# PROC054D_AWR_2_AWR_3_LC_Filtering.net
KiCad netlist of a schematic drawn in Altium Designer
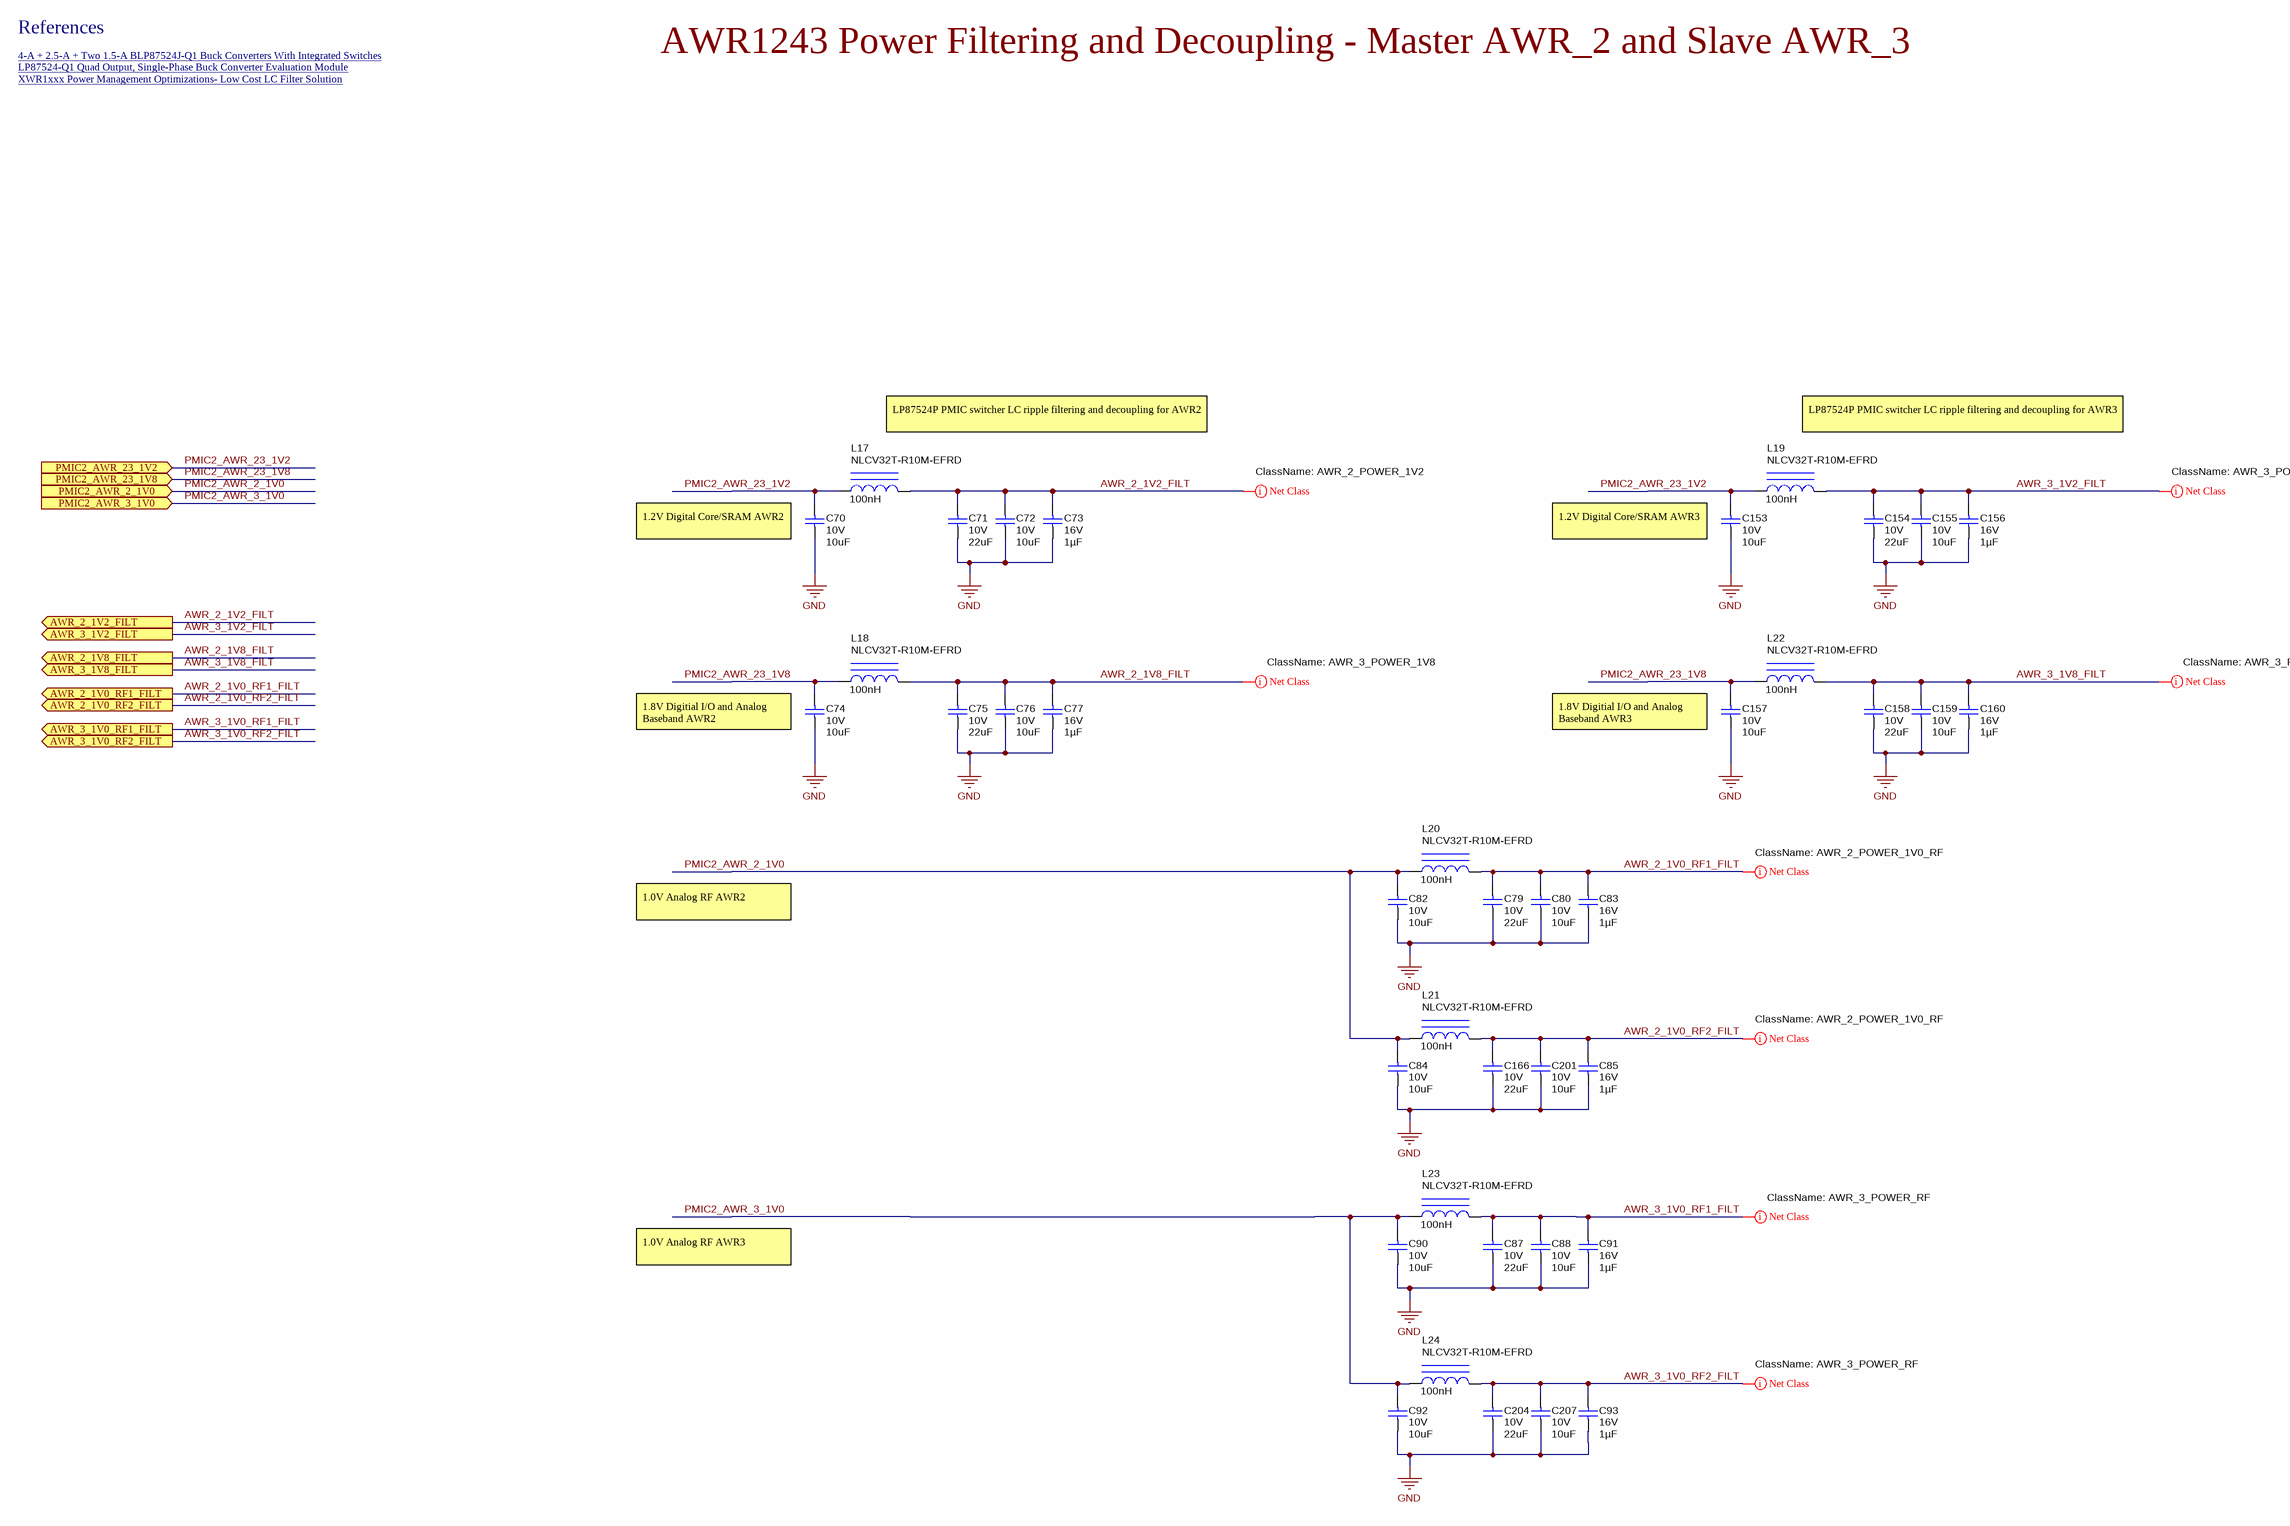
[diagram p0: PROC054D_AWR_2_AWR_3_LC_Filtering.SchDoc]

(export (version "E")
  (design (tool "Eeschema 10.0.6"))
  (components
    (comp (ref "C70")
      (value "GCM21BR71A106KE22L")
      (footprint "0805L")
      (description "CAP, CERM, 10 uF, 10 V, +/- 10%, X7R, 0805")
      (fields
        (field (name "MANUFACTURER") "MuRata")
        (field (name "VDC_V") "10V")
        (field (name "VALUEDISPLAYED") "10uF")
        (field (name "PUBLISHER") "Texas Instruments")
      )
      (libsource (lib "Altium Vault - TI") (part "Capacitor"))
    )
    (comp (ref "C71")
      (value "GCM31CR71A226KE02")
      (footprint "1206_180L")
      (description "CAP, CERM, 22 uF, 10 V, +/- 10%, X7R, AEC-Q200 Grade 1, 1206")
      (fields
        (field (name "MANUFACTURER") "MuRata")
        (field (name "VDC_V") "10V")
        (field (name "VALUEDISPLAYED") "22uF")
        (field (name "PUBLISHER") "Texas Instruments")
      )
      (libsource (lib "Altium Vault - TI") (part "Capacitor"))
    )
    (comp (ref "C72")
      (value "GCM21BR71A106KE22L")
      (footprint "0805L")
      (description "CAP, CERM, 10 uF, 10 V, +/- 10%, X7R, 0805")
      (fields
        (field (name "MANUFACTURER") "MuRata")
        (field (name "VDC_V") "10V")
        (field (name "VALUEDISPLAYED") "10uF")
        (field (name "PUBLISHER") "Texas Instruments")
      )
      (libsource (lib "Altium Vault - TI") (part "Capacitor"))
    )
    (comp (ref "C73")
      (value "GCM188R71C105KA64J")
      (footprint "0603S")
      (description "CAP, CERM, 1 µF, 16 V,+/- 10%, X7R, AEC-Q200 Grade 1, 0603")
      (fields
        (field (name "MANUFACTURER") "MuRata")
        (field (name "VDC_V") "16V")
        (field (name "VALUEDISPLAYED") "1µF")
      )
      (libsource (lib "Altium Vault - TI") (part "Capacitor"))
    )
    (comp (ref "C74")
      (value "GCM21BR71A106KE22L")
      (footprint "0805L")
      (description "CAP, CERM, 10 uF, 10 V, +/- 10%, X7R, 0805")
      (fields
        (field (name "MANUFACTURER") "MuRata")
        (field (name "VDC_V") "10V")
        (field (name "VALUEDISPLAYED") "10uF")
        (field (name "PUBLISHER") "Texas Instruments")
      )
      (libsource (lib "Altium Vault - TI") (part "Capacitor"))
    )
    (comp (ref "C75")
      (value "GCM31CR71A226KE02")
      (footprint "1206_180L")
      (description "CAP, CERM, 22 uF, 10 V, +/- 10%, X7R, AEC-Q200 Grade 1, 1206")
      (fields
        (field (name "MANUFACTURER") "MuRata")
        (field (name "VDC_V") "10V")
        (field (name "VALUEDISPLAYED") "22uF")
        (field (name "PUBLISHER") "Texas Instruments")
      )
      (libsource (lib "Altium Vault - TI") (part "Capacitor"))
    )
    (comp (ref "C76")
      (value "GCM21BR71A106KE22L")
      (footprint "0805L")
      (description "CAP, CERM, 10 uF, 10 V, +/- 10%, X7R, 0805")
      (fields
        (field (name "MANUFACTURER") "MuRata")
        (field (name "VDC_V") "10V")
        (field (name "VALUEDISPLAYED") "10uF")
        (field (name "PUBLISHER") "Texas Instruments")
      )
      (libsource (lib "Altium Vault - TI") (part "Capacitor"))
    )
    (comp (ref "C77")
      (value "GCM188R71C105KA64J")
      (footprint "0603S")
      (description "CAP, CERM, 1 µF, 16 V,+/- 10%, X7R, AEC-Q200 Grade 1, 0603")
      (fields
        (field (name "MANUFACTURER") "MuRata")
        (field (name "VDC_V") "16V")
        (field (name "VALUEDISPLAYED") "1µF")
      )
      (libsource (lib "Altium Vault - TI") (part "Capacitor"))
    )
    (comp (ref "C79")
      (value "GCM31CR71A226KE02")
      (footprint "1206_180L")
      (description "CAP, CERM, 22 uF, 10 V, +/- 10%, X7R, AEC-Q200 Grade 1, 1206")
      (fields
        (field (name "MANUFACTURER") "MuRata")
        (field (name "VDC_V") "10V")
        (field (name "VALUEDISPLAYED") "22uF")
        (field (name "PUBLISHER") "Texas Instruments")
      )
      (libsource (lib "Altium Vault - TI") (part "Capacitor"))
    )
    (comp (ref "C80")
      (value "GCM21BR71A106KE22L")
      (footprint "0805L")
      (description "CAP, CERM, 10 uF, 10 V, +/- 10%, X7R, 0805")
      (fields
        (field (name "MANUFACTURER") "MuRata")
        (field (name "VDC_V") "10V")
        (field (name "VALUEDISPLAYED") "10uF")
        (field (name "PUBLISHER") "Texas Instruments")
      )
      (libsource (lib "Altium Vault - TI") (part "Capacitor"))
    )
    (comp (ref "C82")
      (value "GCM21BR71A106KE22L")
      (footprint "0805L")
      (description "CAP, CERM, 10 uF, 10 V, +/- 10%, X7R, 0805")
      (fields
        (field (name "MANUFACTURER") "MuRata")
        (field (name "VDC_V") "10V")
        (field (name "VALUEDISPLAYED") "10uF")
        (field (name "PUBLISHER") "Texas Instruments")
      )
      (libsource (lib "Altium Vault - TI") (part "Capacitor"))
    )
    (comp (ref "C83")
      (value "GCM188R71C105KA64J")
      (footprint "0603S")
      (description "CAP, CERM, 1 µF, 16 V,+/- 10%, X7R, AEC-Q200 Grade 1, 0603")
      (fields
        (field (name "MANUFACTURER") "MuRata")
        (field (name "VDC_V") "16V")
        (field (name "VALUEDISPLAYED") "1µF")
      )
      (libsource (lib "Altium Vault - TI") (part "Capacitor"))
    )
    (comp (ref "C84")
      (value "GCM21BR71A106KE22L")
      (footprint "0805L")
      (description "CAP, CERM, 10 uF, 10 V, +/- 10%, X7R, 0805")
      (fields
        (field (name "MANUFACTURER") "MuRata")
        (field (name "VDC_V") "10V")
        (field (name "VALUEDISPLAYED") "10uF")
        (field (name "PUBLISHER") "Texas Instruments")
      )
      (libsource (lib "Altium Vault - TI") (part "Capacitor"))
    )
    (comp (ref "C85")
      (value "GCM188R71C105KA64J")
      (footprint "0603S")
      (description "CAP, CERM, 1 µF, 16 V,+/- 10%, X7R, AEC-Q200 Grade 1, 0603")
      (fields
        (field (name "MANUFACTURER") "MuRata")
        (field (name "VDC_V") "16V")
        (field (name "VALUEDISPLAYED") "1µF")
      )
      (libsource (lib "Altium Vault - TI") (part "Capacitor"))
    )
    (comp (ref "C87")
      (value "GCM31CR71A226KE02")
      (footprint "1206_180L")
      (description "CAP, CERM, 22 uF, 10 V, +/- 10%, X7R, AEC-Q200 Grade 1, 1206")
      (fields
        (field (name "MANUFACTURER") "MuRata")
        (field (name "VDC_V") "10V")
        (field (name "VALUEDISPLAYED") "22uF")
        (field (name "PUBLISHER") "Texas Instruments")
      )
      (libsource (lib "Altium Vault - TI") (part "Capacitor"))
    )
    (comp (ref "C88")
      (value "GCM21BR71A106KE22L")
      (footprint "0805L")
      (description "CAP, CERM, 10 uF, 10 V, +/- 10%, X7R, 0805")
      (fields
        (field (name "MANUFACTURER") "MuRata")
        (field (name "VDC_V") "10V")
        (field (name "VALUEDISPLAYED") "10uF")
        (field (name "PUBLISHER") "Texas Instruments")
      )
      (libsource (lib "Altium Vault - TI") (part "Capacitor"))
    )
    (comp (ref "C90")
      (value "GCM21BR71A106KE22L")
      (footprint "0805L")
      (description "CAP, CERM, 10 uF, 10 V, +/- 10%, X7R, 0805")
      (fields
        (field (name "MANUFACTURER") "MuRata")
        (field (name "VDC_V") "10V")
        (field (name "VALUEDISPLAYED") "10uF")
        (field (name "PUBLISHER") "Texas Instruments")
      )
      (libsource (lib "Altium Vault - TI") (part "Capacitor"))
    )
    (comp (ref "C91")
      (value "GCM188R71C105KA64J")
      (footprint "0603S")
      (description "CAP, CERM, 1 µF, 16 V,+/- 10%, X7R, AEC-Q200 Grade 1, 0603")
      (fields
        (field (name "MANUFACTURER") "MuRata")
        (field (name "VDC_V") "16V")
        (field (name "VALUEDISPLAYED") "1µF")
      )
      (libsource (lib "Altium Vault - TI") (part "Capacitor"))
    )
    (comp (ref "C92")
      (value "GCM21BR71A106KE22L")
      (footprint "0805L")
      (description "CAP, CERM, 10 uF, 10 V, +/- 10%, X7R, 0805")
      (fields
        (field (name "MANUFACTURER") "MuRata")
        (field (name "VDC_V") "10V")
        (field (name "VALUEDISPLAYED") "10uF")
        (field (name "PUBLISHER") "Texas Instruments")
      )
      (libsource (lib "Altium Vault - TI") (part "Capacitor"))
    )
    (comp (ref "C93")
      (value "GCM188R71C105KA64J")
      (footprint "0603S")
      (description "CAP, CERM, 1 µF, 16 V,+/- 10%, X7R, AEC-Q200 Grade 1, 0603")
      (fields
        (field (name "MANUFACTURER") "MuRata")
        (field (name "VDC_V") "16V")
        (field (name "VALUEDISPLAYED") "1µF")
      )
      (libsource (lib "Altium Vault - TI") (part "Capacitor"))
    )
    (comp (ref "C153")
      (value "GCM21BR71A106KE22L")
      (footprint "0805L")
      (description "CAP, CERM, 10 uF, 10 V, +/- 10%, X7R, 0805")
      (fields
        (field (name "MANUFACTURER") "MuRata")
        (field (name "VDC_V") "10V")
        (field (name "VALUEDISPLAYED") "10uF")
        (field (name "PUBLISHER") "Texas Instruments")
      )
      (libsource (lib "Altium Vault - TI") (part "Capacitor"))
    )
    (comp (ref "C154")
      (value "GCM31CR71A226KE02")
      (footprint "1206_180L")
      (description "CAP, CERM, 22 uF, 10 V, +/- 10%, X7R, AEC-Q200 Grade 1, 1206")
      (fields
        (field (name "MANUFACTURER") "MuRata")
        (field (name "VDC_V") "10V")
        (field (name "VALUEDISPLAYED") "22uF")
        (field (name "PUBLISHER") "Texas Instruments")
      )
      (libsource (lib "Altium Vault - TI") (part "Capacitor"))
    )
    (comp (ref "C155")
      (value "GCM21BR71A106KE22L")
      (footprint "0805L")
      (description "CAP, CERM, 10 uF, 10 V, +/- 10%, X7R, 0805")
      (fields
        (field (name "MANUFACTURER") "MuRata")
        (field (name "VDC_V") "10V")
        (field (name "VALUEDISPLAYED") "10uF")
        (field (name "PUBLISHER") "Texas Instruments")
      )
      (libsource (lib "Altium Vault - TI") (part "Capacitor"))
    )
    (comp (ref "C156")
      (value "GCM188R71C105KA64J")
      (footprint "0603S")
      (description "CAP, CERM, 1 µF, 16 V,+/- 10%, X7R, AEC-Q200 Grade 1, 0603")
      (fields
        (field (name "MANUFACTURER") "MuRata")
        (field (name "VDC_V") "16V")
        (field (name "VALUEDISPLAYED") "1µF")
      )
      (libsource (lib "Altium Vault - TI") (part "Capacitor"))
    )
    (comp (ref "C157")
      (value "GCM21BR71A106KE22L")
      (footprint "0805L")
      (description "CAP, CERM, 10 uF, 10 V, +/- 10%, X7R, 0805")
      (fields
        (field (name "MANUFACTURER") "MuRata")
        (field (name "VDC_V") "10V")
        (field (name "VALUEDISPLAYED") "10uF")
        (field (name "PUBLISHER") "Texas Instruments")
      )
      (libsource (lib "Altium Vault - TI") (part "Capacitor"))
    )
    (comp (ref "C158")
      (value "GCM31CR71A226KE02")
      (footprint "1206_180L")
      (description "CAP, CERM, 22 uF, 10 V, +/- 10%, X7R, AEC-Q200 Grade 1, 1206")
      (fields
        (field (name "MANUFACTURER") "MuRata")
        (field (name "VDC_V") "10V")
        (field (name "VALUEDISPLAYED") "22uF")
        (field (name "PUBLISHER") "Texas Instruments")
      )
      (libsource (lib "Altium Vault - TI") (part "Capacitor"))
    )
    (comp (ref "C159")
      (value "GCM21BR71A106KE22L")
      (footprint "0805L")
      (description "CAP, CERM, 10 uF, 10 V, +/- 10%, X7R, 0805")
      (fields
        (field (name "MANUFACTURER") "MuRata")
        (field (name "VDC_V") "10V")
        (field (name "VALUEDISPLAYED") "10uF")
        (field (name "PUBLISHER") "Texas Instruments")
      )
      (libsource (lib "Altium Vault - TI") (part "Capacitor"))
    )
    (comp (ref "C160")
      (value "GCM188R71C105KA64J")
      (footprint "0603S")
      (description "CAP, CERM, 1 µF, 16 V,+/- 10%, X7R, AEC-Q200 Grade 1, 0603")
      (fields
        (field (name "MANUFACTURER") "MuRata")
        (field (name "VDC_V") "16V")
        (field (name "VALUEDISPLAYED") "1µF")
      )
      (libsource (lib "Altium Vault - TI") (part "Capacitor"))
    )
    (comp (ref "C166")
      (value "GCM31CR71A226KE02")
      (footprint "1206_180L")
      (description "CAP, CERM, 22 uF, 10 V, +/- 10%, X7R, AEC-Q200 Grade 1, 1206")
      (fields
        (field (name "MANUFACTURER") "MuRata")
        (field (name "VDC_V") "10V")
        (field (name "VALUEDISPLAYED") "22uF")
        (field (name "PUBLISHER") "Texas Instruments")
      )
      (libsource (lib "Altium Vault - TI") (part "Capacitor"))
    )
    (comp (ref "C201")
      (value "GCM21BR71A106KE22L")
      (footprint "0805L")
      (description "CAP, CERM, 10 uF, 10 V, +/- 10%, X7R, 0805")
      (fields
        (field (name "MANUFACTURER") "MuRata")
        (field (name "VDC_V") "10V")
        (field (name "VALUEDISPLAYED") "10uF")
        (field (name "PUBLISHER") "Texas Instruments")
      )
      (libsource (lib "Altium Vault - TI") (part "Capacitor"))
    )
    (comp (ref "C204")
      (value "GCM31CR71A226KE02")
      (footprint "1206_180L")
      (description "CAP, CERM, 22 uF, 10 V, +/- 10%, X7R, AEC-Q200 Grade 1, 1206")
      (fields
        (field (name "MANUFACTURER") "MuRata")
        (field (name "VDC_V") "10V")
        (field (name "VALUEDISPLAYED") "22uF")
        (field (name "PUBLISHER") "Texas Instruments")
      )
      (libsource (lib "Altium Vault - TI") (part "Capacitor"))
    )
    (comp (ref "C207")
      (value "GCM21BR71A106KE22L")
      (footprint "0805L")
      (description "CAP, CERM, 10 uF, 10 V, +/- 10%, X7R, 0805")
      (fields
        (field (name "MANUFACTURER") "MuRata")
        (field (name "VDC_V") "10V")
        (field (name "VALUEDISPLAYED") "10uF")
        (field (name "PUBLISHER") "Texas Instruments")
      )
      (libsource (lib "Altium Vault - TI") (part "Capacitor"))
    )
    (comp (ref "L17")
      (value "NLCV32T-R10M-EFRD")
      (footprint "NLCV32")
      (description "Inductor, Wirewound, Ferrite, 100 nH, 2.85 A, 0.024 ohm, AEC-Q200 Grade 1, SMD")
      (fields
        (field (name "MANUFACTURER") "TDK")
        (field (name "PARTNUMBER") "NLCV32T-R10M-EFRD")
        (field (name "VALUEDISPLAYED") "100nH")
      )
      (libsource (lib "Altium Vault - TI") (part "CMP-0083745-1"))
    )
    (comp (ref "L18")
      (value "NLCV32T-R10M-EFRD")
      (footprint "NLCV32")
      (description "Inductor, Wirewound, Ferrite, 100 nH, 2.85 A, 0.024 ohm, AEC-Q200 Grade 1, SMD")
      (fields
        (field (name "MANUFACTURER") "TDK")
        (field (name "PARTNUMBER") "NLCV32T-R10M-EFRD")
        (field (name "VALUEDISPLAYED") "100nH")
      )
      (libsource (lib "Altium Vault - TI") (part "CMP-0083745-1"))
    )
    (comp (ref "L19")
      (value "NLCV32T-R10M-EFRD")
      (footprint "NLCV32")
      (description "Inductor, Wirewound, Ferrite, 100 nH, 2.85 A, 0.024 ohm, AEC-Q200 Grade 1, SMD")
      (fields
        (field (name "MANUFACTURER") "TDK")
        (field (name "PARTNUMBER") "NLCV32T-R10M-EFRD")
        (field (name "VALUEDISPLAYED") "100nH")
      )
      (libsource (lib "Altium Vault - TI") (part "CMP-0083745-1"))
    )
    (comp (ref "L20")
      (value "NLCV32T-R10M-EFRD")
      (footprint "NLCV32")
      (description "Inductor, Wirewound, Ferrite, 100 nH, 2.85 A, 0.024 ohm, AEC-Q200 Grade 1, SMD")
      (fields
        (field (name "MANUFACTURER") "TDK")
        (field (name "PARTNUMBER") "NLCV32T-R10M-EFRD")
        (field (name "VALUEDISPLAYED") "100nH")
      )
      (libsource (lib "Altium Vault - TI") (part "CMP-0083745-1"))
    )
    (comp (ref "L21")
      (value "NLCV32T-R10M-EFRD")
      (footprint "NLCV32")
      (description "Inductor, Wirewound, Ferrite, 100 nH, 2.85 A, 0.024 ohm, AEC-Q200 Grade 1, SMD")
      (fields
        (field (name "MANUFACTURER") "TDK")
        (field (name "PARTNUMBER") "NLCV32T-R10M-EFRD")
        (field (name "VALUEDISPLAYED") "100nH")
      )
      (libsource (lib "Altium Vault - TI") (part "CMP-0083745-1"))
    )
    (comp (ref "L22")
      (value "NLCV32T-R10M-EFRD")
      (footprint "NLCV32")
      (description "Inductor, Wirewound, Ferrite, 100 nH, 2.85 A, 0.024 ohm, AEC-Q200 Grade 1, SMD")
      (fields
        (field (name "MANUFACTURER") "TDK")
        (field (name "PARTNUMBER") "NLCV32T-R10M-EFRD")
        (field (name "VALUEDISPLAYED") "100nH")
      )
      (libsource (lib "Altium Vault - TI") (part "CMP-0083745-1"))
    )
    (comp (ref "L23")
      (value "NLCV32T-R10M-EFRD")
      (footprint "NLCV32")
      (description "Inductor, Wirewound, Ferrite, 100 nH, 2.85 A, 0.024 ohm, AEC-Q200 Grade 1, SMD")
      (fields
        (field (name "MANUFACTURER") "TDK")
        (field (name "PARTNUMBER") "NLCV32T-R10M-EFRD")
        (field (name "VALUEDISPLAYED") "100nH")
      )
      (libsource (lib "Altium Vault - TI") (part "CMP-0083745-1"))
    )
    (comp (ref "L24")
      (value "NLCV32T-R10M-EFRD")
      (footprint "NLCV32")
      (description "Inductor, Wirewound, Ferrite, 100 nH, 2.85 A, 0.024 ohm, AEC-Q200 Grade 1, SMD")
      (fields
        (field (name "MANUFACTURER") "TDK")
        (field (name "PARTNUMBER") "NLCV32T-R10M-EFRD")
        (field (name "VALUEDISPLAYED") "100nH")
      )
      (libsource (lib "Altium Vault - TI") (part "CMP-0083745-1"))
    )
  )
  (nets
    (net (code "1") (name "/AWR_2_1V0_RF1_FILT") (class "Default")
      (node (ref "C79") (pin "1") (pinfunction "1_1") (pintype "passive"))
      (node (ref "C80") (pin "1") (pinfunction "1_1") (pintype "passive"))
      (node (ref "C83") (pin "1") (pinfunction "1_1") (pintype "passive"))
      (node (ref "L20") (pin "2") (pinfunction "2_2") (pintype "passive"))
    )
    (net (code "2") (name "/AWR_2_1V0_RF2_FILT") (class "Default")
      (node (ref "C166") (pin "1") (pinfunction "1_1") (pintype "passive"))
      (node (ref "C201") (pin "1") (pinfunction "1_1") (pintype "passive"))
      (node (ref "C85") (pin "1") (pinfunction "1_1") (pintype "passive"))
      (node (ref "L21") (pin "2") (pinfunction "2_2") (pintype "passive"))
    )
    (net (code "3") (name "/AWR_2_1V2_FILT") (class "Default")
      (node (ref "C71") (pin "1") (pinfunction "1_1") (pintype "passive"))
      (node (ref "C72") (pin "1") (pinfunction "1_1") (pintype "passive"))
      (node (ref "C73") (pin "1") (pinfunction "1_1") (pintype "passive"))
      (node (ref "L17") (pin "2") (pinfunction "2_2") (pintype "passive"))
    )
    (net (code "4") (name "/AWR_2_1V8_FILT") (class "Default")
      (node (ref "C75") (pin "1") (pinfunction "1_1") (pintype "passive"))
      (node (ref "C76") (pin "1") (pinfunction "1_1") (pintype "passive"))
      (node (ref "C77") (pin "1") (pinfunction "1_1") (pintype "passive"))
      (node (ref "L18") (pin "2") (pinfunction "2_2") (pintype "passive"))
    )
    (net (code "5") (name "/AWR_3_1V0_RF1_FILT") (class "Default")
      (node (ref "C87") (pin "1") (pinfunction "1_1") (pintype "passive"))
      (node (ref "C88") (pin "1") (pinfunction "1_1") (pintype "passive"))
      (node (ref "C91") (pin "1") (pinfunction "1_1") (pintype "passive"))
      (node (ref "L23") (pin "2") (pinfunction "2_2") (pintype "passive"))
    )
    (net (code "6") (name "/AWR_3_1V0_RF2_FILT") (class "Default")
      (node (ref "C204") (pin "1") (pinfunction "1_1") (pintype "passive"))
      (node (ref "C207") (pin "1") (pinfunction "1_1") (pintype "passive"))
      (node (ref "C93") (pin "1") (pinfunction "1_1") (pintype "passive"))
      (node (ref "L24") (pin "2") (pinfunction "2_2") (pintype "passive"))
    )
    (net (code "7") (name "/AWR_3_1V2_FILT") (class "Default")
      (node (ref "C154") (pin "1") (pinfunction "1_1") (pintype "passive"))
      (node (ref "C155") (pin "1") (pinfunction "1_1") (pintype "passive"))
      (node (ref "C156") (pin "1") (pinfunction "1_1") (pintype "passive"))
      (node (ref "L19") (pin "2") (pinfunction "2_2") (pintype "passive"))
    )
    (net (code "8") (name "/AWR_3_1V8_FILT") (class "Default")
      (node (ref "C158") (pin "1") (pinfunction "1_1") (pintype "passive"))
      (node (ref "C159") (pin "1") (pinfunction "1_1") (pintype "passive"))
      (node (ref "C160") (pin "1") (pinfunction "1_1") (pintype "passive"))
      (node (ref "L22") (pin "2") (pinfunction "2_2") (pintype "passive"))
    )
    (net (code "9") (name "/PMIC2_AWR_2_1V0") (class "Default")
      (node (ref "C82") (pin "1") (pinfunction "1_1") (pintype "passive"))
      (node (ref "C84") (pin "1") (pinfunction "1_1") (pintype "passive"))
      (node (ref "L20") (pin "1") (pinfunction "1_1") (pintype "passive"))
      (node (ref "L21") (pin "1") (pinfunction "1_1") (pintype "passive"))
    )
    (net (code "10") (name "/PMIC2_AWR_3_1V0") (class "Default")
      (node (ref "C90") (pin "1") (pinfunction "1_1") (pintype "passive"))
      (node (ref "C92") (pin "1") (pinfunction "1_1") (pintype "passive"))
      (node (ref "L23") (pin "1") (pinfunction "1_1") (pintype "passive"))
      (node (ref "L24") (pin "1") (pinfunction "1_1") (pintype "passive"))
    )
    (net (code "11") (name "/PMIC2_AWR_23_1V2") (class "Default")
      (node (ref "C153") (pin "1") (pinfunction "1_1") (pintype "passive"))
      (node (ref "C70") (pin "1") (pinfunction "1_1") (pintype "passive"))
      (node (ref "L17") (pin "1") (pinfunction "1_1") (pintype "passive"))
      (node (ref "L19") (pin "1") (pinfunction "1_1") (pintype "passive"))
    )
    (net (code "12") (name "/PMIC2_AWR_23_1V8") (class "Default")
      (node (ref "C157") (pin "1") (pinfunction "1_1") (pintype "passive"))
      (node (ref "C74") (pin "1") (pinfunction "1_1") (pintype "passive"))
      (node (ref "L18") (pin "1") (pinfunction "1_1") (pintype "passive"))
      (node (ref "L22") (pin "1") (pinfunction "1_1") (pintype "passive"))
    )
    (net (code "13") (name "GND") (class "Default")
      (node (ref "C153") (pin "2") (pinfunction "2_2") (pintype "passive"))
      (node (ref "C154") (pin "2") (pinfunction "2_2") (pintype "passive"))
      (node (ref "C155") (pin "2") (pinfunction "2_2") (pintype "passive"))
      (node (ref "C156") (pin "2") (pinfunction "2_2") (pintype "passive"))
      (node (ref "C157") (pin "2") (pinfunction "2_2") (pintype "passive"))
      (node (ref "C158") (pin "2") (pinfunction "2_2") (pintype "passive"))
      (node (ref "C159") (pin "2") (pinfunction "2_2") (pintype "passive"))
      (node (ref "C160") (pin "2") (pinfunction "2_2") (pintype "passive"))
      (node (ref "C166") (pin "2") (pinfunction "2_2") (pintype "passive"))
      (node (ref "C201") (pin "2") (pinfunction "2_2") (pintype "passive"))
      (node (ref "C204") (pin "2") (pinfunction "2_2") (pintype "passive"))
      (node (ref "C207") (pin "2") (pinfunction "2_2") (pintype "passive"))
      (node (ref "C70") (pin "2") (pinfunction "2_2") (pintype "passive"))
      (node (ref "C71") (pin "2") (pinfunction "2_2") (pintype "passive"))
      (node (ref "C72") (pin "2") (pinfunction "2_2") (pintype "passive"))
      (node (ref "C73") (pin "2") (pinfunction "2_2") (pintype "passive"))
      (node (ref "C74") (pin "2") (pinfunction "2_2") (pintype "passive"))
      (node (ref "C75") (pin "2") (pinfunction "2_2") (pintype "passive"))
      (node (ref "C76") (pin "2") (pinfunction "2_2") (pintype "passive"))
      (node (ref "C77") (pin "2") (pinfunction "2_2") (pintype "passive"))
      (node (ref "C79") (pin "2") (pinfunction "2_2") (pintype "passive"))
      (node (ref "C80") (pin "2") (pinfunction "2_2") (pintype "passive"))
      (node (ref "C82") (pin "2") (pinfunction "2_2") (pintype "passive"))
      (node (ref "C83") (pin "2") (pinfunction "2_2") (pintype "passive"))
      (node (ref "C84") (pin "2") (pinfunction "2_2") (pintype "passive"))
      (node (ref "C85") (pin "2") (pinfunction "2_2") (pintype "passive"))
      (node (ref "C87") (pin "2") (pinfunction "2_2") (pintype "passive"))
      (node (ref "C88") (pin "2") (pinfunction "2_2") (pintype "passive"))
      (node (ref "C90") (pin "2") (pinfunction "2_2") (pintype "passive"))
      (node (ref "C91") (pin "2") (pinfunction "2_2") (pintype "passive"))
      (node (ref "C92") (pin "2") (pinfunction "2_2") (pintype "passive"))
      (node (ref "C93") (pin "2") (pinfunction "2_2") (pintype "passive"))
    )
  )
)
